# NRF52832_MODULE_V1_0_D.net
KiCad netlist of a schematic drawn in Altium Designer
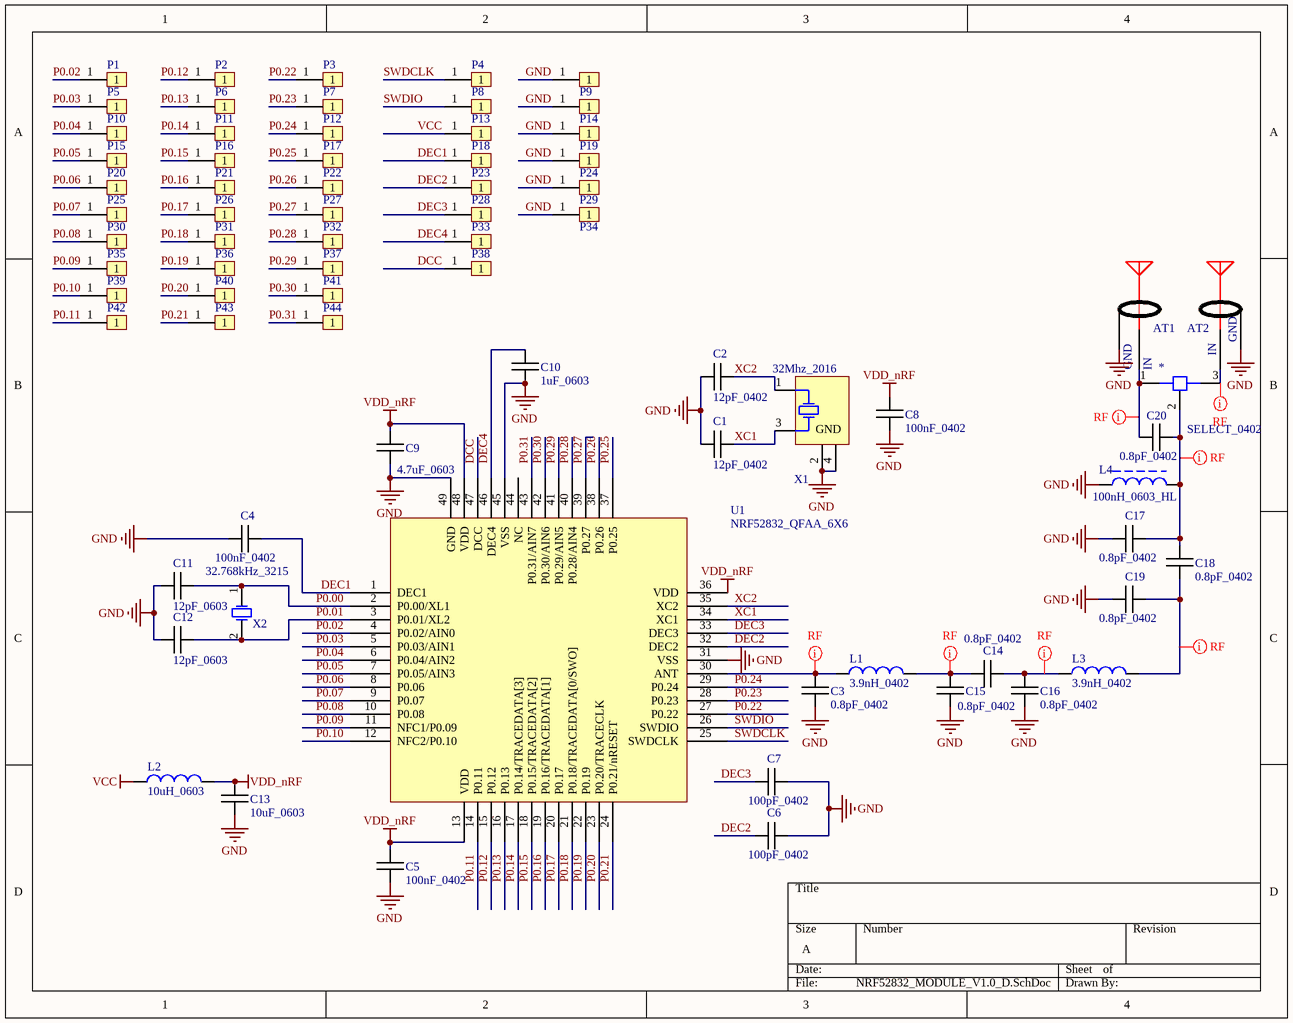
[diagram p0: NRF52832_MODULE_V1.0_D.SchDoc]

(export (version "E")
  (design (tool "Eeschema 10.0.6"))
  (components
    (comp (ref "*")
      (value "SELECT_0402")
      (footprint "PAD 0402_SELECT")
      (libsource (lib "PO_LIBRARY") (part "SELECT_0402"))
    )
    (comp (ref "AT1")
      (value "ANTEN_PCB")
      (footprint "ANTEN_PCB_15MM_L")
      (description "ANTEN_PCB_15MM")
      (libsource (lib "PO_LIBRARY") (part "ANTEN_PCB"))
    )
    (comp (ref "AT2")
      (value "IPX_KK23011-32-7H")
      (footprint "IPEX_ANTENNA")
      (description "ANTEN IPX KK23011-32-7H FOXCONN")
      (libsource (lib "PO_LIBRARY") (part "ANTEN_IPX"))
    )
    (comp (ref "C1")
      (value "12pF_0402")
      (footprint "CAP 0402")
      (libsource (lib "PO_LIBRARY") (part "12pF_0402"))
    )
    (comp (ref "C2")
      (value "12pF_0402")
      (footprint "CAP 0402")
      (libsource (lib "PO_LIBRARY") (part "12pF_0402"))
    )
    (comp (ref "C3")
      (value "0.8pF_0402")
      (footprint "CAP 0402")
      (libsource (lib "PO_LIBRARY") (part "0.8pF_0402"))
    )
    (comp (ref "C4")
      (value "100nF_0402")
      (footprint "CAP 0402")
      (description "104_100nF_0402")
      (libsource (lib "PO_LIBRARY") (part "104_100nF_0402"))
    )
    (comp (ref "C5")
      (value "100nF_0402")
      (footprint "CAP 0402")
      (description "104_100nF_0402")
      (libsource (lib "PO_LIBRARY") (part "104_100nF_0402"))
    )
    (comp (ref "C6")
      (value "100pF_0402")
      (footprint "CAP 0402")
      (description "101_100pF_0402")
      (libsource (lib "PO_LIBRARY") (part "101_100pF_0402"))
    )
    (comp (ref "C7")
      (value "100pF_0402")
      (footprint "CAP 0402")
      (description "101_100pF_0402")
      (libsource (lib "PO_LIBRARY") (part "101_100pF_0402"))
    )
    (comp (ref "C8")
      (value "100nF_0402")
      (footprint "CAP 0402")
      (description "104_100nF_0402")
      (libsource (lib "PO_LIBRARY") (part "104_100nF_0402"))
    )
    (comp (ref "C9")
      (value "4.7uF_0603")
      (footprint "CAP 0603")
      (libsource (lib "PO_LIBRARY") (part "4.7uF_0603"))
    )
    (comp (ref "C10")
      (value "1uF_0603")
      (footprint "CAP 0603")
      (description "1uF_0603 16V")
      (libsource (lib "PO_LIBRARY") (part "105_1uF_0603"))
    )
    (comp (ref "C11")
      (value "12pF_0603")
      (footprint "CAP 0402")
      (description "12pF_0402")
      (libsource (lib "PO_LIBRARY") (part "12pF_0402"))
    )
    (comp (ref "C12")
      (value "12pF_0603")
      (footprint "CAP 0402")
      (description "12pF_0402")
      (libsource (lib "PO_LIBRARY") (part "12pF_0402"))
    )
    (comp (ref "C13")
      (value "10uF_0603")
      (footprint "CAP 0603")
      (description "10uF_0603 16V")
      (libsource (lib "PO_LIBRARY") (part "106_10uF_0603"))
    )
    (comp (ref "C14")
      (value "0.8pF_0402")
      (footprint "CAP 0402")
      (libsource (lib "PO_LIBRARY") (part "0.8pF_0402"))
    )
    (comp (ref "C15")
      (value "0.8pF_0402")
      (footprint "CAP 0402")
      (libsource (lib "PO_LIBRARY") (part "0.8pF_0402"))
    )
    (comp (ref "C16")
      (value "0.8pF_0402")
      (footprint "CAP 0402")
      (libsource (lib "PO_LIBRARY") (part "0.8pF_0402"))
    )
    (comp (ref "C17")
      (value "0.8pF_0402")
      (footprint "CAP 0402")
      (libsource (lib "PO_LIBRARY") (part "0.8pF_0402"))
    )
    (comp (ref "C18")
      (value "0.8pF_0402")
      (footprint "CAP 0402")
      (libsource (lib "PO_LIBRARY") (part "0.8pF_0402"))
    )
    (comp (ref "C19")
      (value "0.8pF_0402")
      (footprint "CAP 0402")
      (libsource (lib "PO_LIBRARY") (part "0.8pF_0402"))
    )
    (comp (ref "C20")
      (value "0.8pF_0402")
      (footprint "CAP 0402")
      (libsource (lib "PO_LIBRARY") (part "0.8pF_0402"))
    )
    (comp (ref "L1")
      (value "3.9nH_0402")
      (footprint "Inductor 0402")
      (libsource (lib "PO_LIBRARY") (part "3.9nH"))
    )
    (comp (ref "L2")
      (value "10uH_0603")
      (footprint "INDUCTOR 0603")
      (libsource (lib "PO_LIBRARY") (part "10uH_0603"))
    )
    (comp (ref "L3")
      (value "3.9nH_0402")
      (footprint "Inductor 0402")
      (libsource (lib "PO_LIBRARY") (part "3.9nH"))
    )
    (comp (ref "L4")
      (value "100nH_0603_HL")
      (footprint "INDUCTOR 0603_HL")
      (description "SDWL1608CR10JSTF Wire Wound Chip Ceramic Inductor")
      (libsource (lib "PO_LIBRARY") (part "100nH_0603_HL"))
    )
    (comp (ref "P1")
      (value "Half-hole 0.6mm")
      (footprint "HALF-HOLE_0.6MM")
      (description "Part Half-hole 0.6mm")
      (libsource (lib "PO_LIBRARY") (part "Half-hole 0.6mm"))
    )
    (comp (ref "P2")
      (value "Half-hole 0.6mm")
      (footprint "HALF-HOLE_0.6MM")
      (description "Part Half-hole 0.6mm")
      (libsource (lib "PO_LIBRARY") (part "Half-hole 0.6mm"))
    )
    (comp (ref "P3")
      (value "Half-hole 0.6mm")
      (footprint "HALF-HOLE_0.6MM")
      (description "Part Half-hole 0.6mm")
      (libsource (lib "PO_LIBRARY") (part "Half-hole 0.6mm"))
    )
    (comp (ref "P4")
      (value "Half-hole 0.6mm")
      (footprint "HALF-HOLE_0.6MM")
      (description "Part Half-hole 0.6mm")
      (libsource (lib "PO_LIBRARY") (part "Half-hole 0.6mm"))
    )
    (comp (ref "P5")
      (value "Half-hole 0.6mm")
      (footprint "HALF-HOLE_0.6MM")
      (description "Part Half-hole 0.6mm")
      (libsource (lib "PO_LIBRARY") (part "Half-hole 0.6mm"))
    )
    (comp (ref "P6")
      (value "Half-hole 0.6mm")
      (footprint "HALF-HOLE_0.6MM")
      (description "Part Half-hole 0.6mm")
      (libsource (lib "PO_LIBRARY") (part "Half-hole 0.6mm"))
    )
    (comp (ref "P7")
      (value "Half-hole 0.6mm")
      (footprint "HALF-HOLE_0.6MM")
      (description "Part Half-hole 0.6mm")
      (libsource (lib "PO_LIBRARY") (part "Half-hole 0.6mm"))
    )
    (comp (ref "P8")
      (value "Half-hole 0.6mm")
      (footprint "HALF-HOLE_0.6MM")
      (description "Part Half-hole 0.6mm")
      (libsource (lib "PO_LIBRARY") (part "Half-hole 0.6mm"))
    )
    (comp (ref "P9")
      (value "Half-hole 0.6mm")
      (footprint "HALF-HOLE_0.6MM")
      (description "Part Half-hole 0.6mm")
      (libsource (lib "PO_LIBRARY") (part "Half-hole 0.6mm"))
    )
    (comp (ref "P10")
      (value "Half-hole 0.6mm")
      (footprint "HALF-HOLE_0.6MM")
      (description "Part Half-hole 0.6mm")
      (libsource (lib "PO_LIBRARY") (part "Half-hole 0.6mm"))
    )
    (comp (ref "P11")
      (value "Half-hole 0.6mm")
      (footprint "HALF-HOLE_0.6MM")
      (description "Part Half-hole 0.6mm")
      (libsource (lib "PO_LIBRARY") (part "Half-hole 0.6mm"))
    )
    (comp (ref "P12")
      (value "Half-hole 0.6mm")
      (footprint "HALF-HOLE_0.6MM")
      (description "Part Half-hole 0.6mm")
      (libsource (lib "PO_LIBRARY") (part "Half-hole 0.6mm"))
    )
    (comp (ref "P13")
      (value "Half-hole 0.6mm")
      (footprint "HALF-HOLE_0.6MM")
      (description "Part Half-hole 0.6mm")
      (libsource (lib "PO_LIBRARY") (part "Half-hole 0.6mm"))
    )
    (comp (ref "P14")
      (value "Half-hole 0.6mm")
      (footprint "HALF-HOLE_0.6MM")
      (description "Part Half-hole 0.6mm")
      (libsource (lib "PO_LIBRARY") (part "Half-hole 0.6mm"))
    )
    (comp (ref "P15")
      (value "Half-hole 0.6mm")
      (footprint "HALF-HOLE_0.6MM")
      (description "Part Half-hole 0.6mm")
      (libsource (lib "PO_LIBRARY") (part "Half-hole 0.6mm"))
    )
    (comp (ref "P16")
      (value "Half-hole 0.6mm")
      (footprint "HALF-HOLE_0.6MM")
      (description "Part Half-hole 0.6mm")
      (libsource (lib "PO_LIBRARY") (part "Half-hole 0.6mm"))
    )
    (comp (ref "P17")
      (value "Half-hole 0.6mm")
      (footprint "HALF-HOLE_0.6MM")
      (description "Part Half-hole 0.6mm")
      (libsource (lib "PO_LIBRARY") (part "Half-hole 0.6mm"))
    )
    (comp (ref "P18")
      (value "Half-hole 0.6mm")
      (footprint "HALF-HOLE_0.6MM")
      (description "Part Half-hole 0.6mm")
      (libsource (lib "PO_LIBRARY") (part "Half-hole 0.6mm"))
    )
    (comp (ref "P19")
      (value "Half-hole 0.6mm")
      (footprint "HALF-HOLE_0.6MM")
      (description "Part Half-hole 0.6mm")
      (libsource (lib "PO_LIBRARY") (part "Half-hole 0.6mm"))
    )
    (comp (ref "P20")
      (value "Half-hole 0.6mm")
      (footprint "HALF-HOLE_0.6MM")
      (description "Part Half-hole 0.6mm")
      (libsource (lib "PO_LIBRARY") (part "Half-hole 0.6mm"))
    )
    (comp (ref "P21")
      (value "Half-hole 0.6mm")
      (footprint "HALF-HOLE_0.6MM")
      (description "Part Half-hole 0.6mm")
      (libsource (lib "PO_LIBRARY") (part "Half-hole 0.6mm"))
    )
    (comp (ref "P22")
      (value "Half-hole 0.6mm")
      (footprint "HALF-HOLE_0.6MM")
      (description "Part Half-hole 0.6mm")
      (libsource (lib "PO_LIBRARY") (part "Half-hole 0.6mm"))
    )
    (comp (ref "P23")
      (value "Half-hole 0.6mm")
      (footprint "HALF-HOLE_0.6MM")
      (description "Part Half-hole 0.6mm")
      (libsource (lib "PO_LIBRARY") (part "Half-hole 0.6mm"))
    )
    (comp (ref "P24")
      (value "Half-hole 0.6mm")
      (footprint "HALF-HOLE_0.6MM")
      (description "Part Half-hole 0.6mm")
      (libsource (lib "PO_LIBRARY") (part "Half-hole 0.6mm"))
    )
    (comp (ref "P25")
      (value "Half-hole 0.6mm")
      (footprint "HALF-HOLE_0.6MM")
      (description "Part Half-hole 0.6mm")
      (libsource (lib "PO_LIBRARY") (part "Half-hole 0.6mm"))
    )
    (comp (ref "P26")
      (value "Half-hole 0.6mm")
      (footprint "HALF-HOLE_0.6MM")
      (description "Part Half-hole 0.6mm")
      (libsource (lib "PO_LIBRARY") (part "Half-hole 0.6mm"))
    )
    (comp (ref "P27")
      (value "Half-hole 0.6mm")
      (footprint "HALF-HOLE_0.6MM")
      (description "Part Half-hole 0.6mm")
      (libsource (lib "PO_LIBRARY") (part "Half-hole 0.6mm"))
    )
    (comp (ref "P28")
      (value "Half-hole 0.6mm")
      (footprint "HALF-HOLE_0.6MM")
      (description "Part Half-hole 0.6mm")
      (libsource (lib "PO_LIBRARY") (part "Half-hole 0.6mm"))
    )
    (comp (ref "P29")
      (value "Half-hole 0.6mm")
      (footprint "HALF-HOLE_0.6MM")
      (description "Part Half-hole 0.6mm")
      (libsource (lib "PO_LIBRARY") (part "Half-hole 0.6mm"))
    )
    (comp (ref "P30")
      (value "Half-hole 0.6mm")
      (footprint "HALF-HOLE_0.6MM")
      (description "Part Half-hole 0.6mm")
      (libsource (lib "PO_LIBRARY") (part "Half-hole 0.6mm"))
    )
    (comp (ref "P31")
      (value "Half-hole 0.6mm")
      (footprint "HALF-HOLE_0.6MM")
      (description "Part Half-hole 0.6mm")
      (libsource (lib "PO_LIBRARY") (part "Half-hole 0.6mm"))
    )
    (comp (ref "P32")
      (value "Half-hole 0.6mm")
      (footprint "HALF-HOLE_0.6MM")
      (description "Part Half-hole 0.6mm")
      (libsource (lib "PO_LIBRARY") (part "Half-hole 0.6mm"))
    )
    (comp (ref "P33")
      (value "Half-hole 0.6mm")
      (footprint "HALF-HOLE_0.6MM")
      (description "Part Half-hole 0.6mm")
      (libsource (lib "PO_LIBRARY") (part "Half-hole 0.6mm"))
    )
    (comp (ref "P34")
      (value "Half-hole 0.6mm")
      (footprint "HALF-HOLE_0.6MM")
      (description "Part Half-hole 0.6mm")
      (libsource (lib "PO_LIBRARY") (part "Half-hole 0.6mm"))
    )
    (comp (ref "P35")
      (value "Half-hole 0.6mm")
      (footprint "HALF-HOLE_0.6MM")
      (description "Part Half-hole 0.6mm")
      (libsource (lib "PO_LIBRARY") (part "Half-hole 0.6mm"))
    )
    (comp (ref "P36")
      (value "Half-hole 0.6mm")
      (footprint "HALF-HOLE_0.6MM")
      (description "Part Half-hole 0.6mm")
      (libsource (lib "PO_LIBRARY") (part "Half-hole 0.6mm"))
    )
    (comp (ref "P37")
      (value "Half-hole 0.6mm")
      (footprint "HALF-HOLE_0.6MM")
      (description "Part Half-hole 0.6mm")
      (libsource (lib "PO_LIBRARY") (part "Half-hole 0.6mm"))
    )
    (comp (ref "P38")
      (value "Half-hole 0.6mm")
      (footprint "HALF-HOLE_0.6MM")
      (description "Part Half-hole 0.6mm")
      (libsource (lib "PO_LIBRARY") (part "Half-hole 0.6mm"))
    )
    (comp (ref "P39")
      (value "Half-hole 0.6mm")
      (footprint "HALF-HOLE_0.6MM")
      (description "Part Half-hole 0.6mm")
      (libsource (lib "PO_LIBRARY") (part "Half-hole 0.6mm"))
    )
    (comp (ref "P40")
      (value "Half-hole 0.6mm")
      (footprint "HALF-HOLE_0.6MM")
      (description "Part Half-hole 0.6mm")
      (libsource (lib "PO_LIBRARY") (part "Half-hole 0.6mm"))
    )
    (comp (ref "P41")
      (value "Half-hole 0.6mm")
      (footprint "HALF-HOLE_0.6MM")
      (description "Part Half-hole 0.6mm")
      (libsource (lib "PO_LIBRARY") (part "Half-hole 0.6mm"))
    )
    (comp (ref "P42")
      (value "Half-hole 0.6mm")
      (footprint "HALF-HOLE_0.6MM")
      (description "Part Half-hole 0.6mm")
      (libsource (lib "PO_LIBRARY") (part "Half-hole 0.6mm"))
    )
    (comp (ref "P43")
      (value "Half-hole 0.6mm")
      (footprint "HALF-HOLE_0.6MM")
      (description "Part Half-hole 0.6mm")
      (libsource (lib "PO_LIBRARY") (part "Half-hole 0.6mm"))
    )
    (comp (ref "P44")
      (value "Half-hole 0.6mm")
      (footprint "HALF-HOLE_0.6MM")
      (description "Part Half-hole 0.6mm")
      (libsource (lib "PO_LIBRARY") (part "Half-hole 0.6mm"))
    )
    (comp (ref "U1")
      (value "NRF52832_QFAA_6X6")
      (footprint "QFN48_6X6")
      (libsource (lib "PO_LIBRARY") (part "NRF52832"))
    )
    (comp (ref "X1")
      (value "32Mhz_2016")
      (footprint "CYSTAL-SMD-2016")
      (libsource (lib "PO_LIBRARY") (part "Crystal 2016 32MHz"))
    )
    (comp (ref "X2")
      (value "32.768kHz_3215")
      (footprint "CYSTAL-SMD-3215")
      (description "Crystal 3215 32.768kHz")
      (libsource (lib "PO_LIBRARY") (part "Crystal 3215 32.768kHz"))
    )
  )
  (nets
    (net (code "1") (name "/DCC") (class "Default")
      (node (ref "P38") (pin "1") (pinfunction "1_1") (pintype "passive"))
      (node (ref "U1") (pin "47") (pinfunction "DCC_47") (pintype "passive"))
    )
    (net (code "2") (name "/DEC1") (class "Default")
      (node (ref "C4") (pin "2") (pinfunction "2_2") (pintype "passive"))
      (node (ref "P18") (pin "1") (pinfunction "1_1") (pintype "passive"))
      (node (ref "U1") (pin "1") (pinfunction "DEC1_1") (pintype "passive"))
    )
    (net (code "3") (name "/DEC2") (class "Default")
      (node (ref "C6") (pin "1") (pinfunction "1_1") (pintype "passive"))
      (node (ref "P23") (pin "1") (pinfunction "1_1") (pintype "passive"))
      (node (ref "U1") (pin "32") (pinfunction "DEC2_32") (pintype "passive"))
    )
    (net (code "4") (name "/DEC3") (class "Default")
      (node (ref "C7") (pin "1") (pinfunction "1_1") (pintype "passive"))
      (node (ref "P28") (pin "1") (pinfunction "1_1") (pintype "passive"))
      (node (ref "U1") (pin "33") (pinfunction "DEC3_33") (pintype "passive"))
    )
    (net (code "5") (name "/DEC4") (class "Default")
      (node (ref "C10") (pin "2") (pinfunction "2_2") (pintype "passive"))
      (node (ref "P33") (pin "1") (pinfunction "1_1") (pintype "passive"))
      (node (ref "U1") (pin "46") (pinfunction "DEC4_46") (pintype "passive"))
    )
    (net (code "6") (name "/P0.00") (class "Default")
      (node (ref "C11") (pin "1") (pinfunction "1_1") (pintype "passive"))
      (node (ref "U1") (pin "2") (pinfunction "P0.00/XL1_2") (pintype "passive"))
      (node (ref "X2") (pin "1") (pinfunction "XTAL_1") (pintype "passive"))
    )
    (net (code "7") (name "/P0.01") (class "Default")
      (node (ref "C12") (pin "1") (pinfunction "1_1") (pintype "passive"))
      (node (ref "U1") (pin "3") (pinfunction "P0.01/XL2_3") (pintype "passive"))
      (node (ref "X2") (pin "2") (pinfunction "XTAL_2") (pintype "passive"))
    )
    (net (code "8") (name "/P0.02") (class "Default")
      (node (ref "P1") (pin "1") (pinfunction "1_1") (pintype "passive"))
      (node (ref "U1") (pin "4") (pinfunction "P0.02/AIN0_4") (pintype "passive"))
    )
    (net (code "9") (name "/P0.03") (class "Default")
      (node (ref "P5") (pin "1") (pinfunction "1_1") (pintype "passive"))
      (node (ref "U1") (pin "5") (pinfunction "P0.03/AIN1_5") (pintype "passive"))
    )
    (net (code "10") (name "/P0.04") (class "Default")
      (node (ref "P10") (pin "1") (pinfunction "1_1") (pintype "passive"))
      (node (ref "U1") (pin "6") (pinfunction "P0.04/AIN2_6") (pintype "passive"))
    )
    (net (code "11") (name "/P0.05") (class "Default")
      (node (ref "P15") (pin "1") (pinfunction "1_1") (pintype "passive"))
      (node (ref "U1") (pin "7") (pinfunction "P0.05/AIN3_7") (pintype "passive"))
    )
    (net (code "12") (name "/P0.06") (class "Default")
      (node (ref "P20") (pin "1") (pinfunction "1_1") (pintype "passive"))
      (node (ref "U1") (pin "8") (pinfunction "P0.06_8") (pintype "passive"))
    )
    (net (code "13") (name "/P0.07") (class "Default")
      (node (ref "P25") (pin "1") (pinfunction "1_1") (pintype "passive"))
      (node (ref "U1") (pin "9") (pinfunction "P0.07_9") (pintype "passive"))
    )
    (net (code "14") (name "/P0.08") (class "Default")
      (node (ref "P30") (pin "1") (pinfunction "1_1") (pintype "passive"))
      (node (ref "U1") (pin "10") (pinfunction "P0.08_10") (pintype "passive"))
    )
    (net (code "15") (name "/P0.09") (class "Default")
      (node (ref "P35") (pin "1") (pinfunction "1_1") (pintype "passive"))
      (node (ref "U1") (pin "11") (pinfunction "NFC1/P0.09_11") (pintype "passive"))
    )
    (net (code "16") (name "/P0.10") (class "Default")
      (node (ref "P39") (pin "1") (pinfunction "1_1") (pintype "passive"))
      (node (ref "U1") (pin "12") (pinfunction "NFC2/P0.10_12") (pintype "passive"))
    )
    (net (code "17") (name "/P0.11") (class "Default")
      (node (ref "P42") (pin "1") (pinfunction "1_1") (pintype "passive"))
      (node (ref "U1") (pin "14") (pinfunction "P0.11_14") (pintype "passive"))
    )
    (net (code "18") (name "/P0.12") (class "Default")
      (node (ref "P2") (pin "1") (pinfunction "1_1") (pintype "passive"))
      (node (ref "U1") (pin "15") (pinfunction "P0.12_15") (pintype "passive"))
    )
    (net (code "19") (name "/P0.13") (class "Default")
      (node (ref "P6") (pin "1") (pinfunction "1_1") (pintype "passive"))
      (node (ref "U1") (pin "16") (pinfunction "P0.13_16") (pintype "passive"))
    )
    (net (code "20") (name "/P0.14") (class "Default")
      (node (ref "P11") (pin "1") (pinfunction "1_1") (pintype "passive"))
      (node (ref "U1") (pin "17") (pinfunction "P0.14/TRACEDATA[3]_17") (pintype "passive"))
    )
    (net (code "21") (name "/P0.15") (class "Default")
      (node (ref "P16") (pin "1") (pinfunction "1_1") (pintype "passive"))
      (node (ref "U1") (pin "18") (pinfunction "P0.15/TRACEDATA[2]_18") (pintype "passive"))
    )
    (net (code "22") (name "/P0.16") (class "Default")
      (node (ref "P21") (pin "1") (pinfunction "1_1") (pintype "passive"))
      (node (ref "U1") (pin "19") (pinfunction "P0.16/TRACEDATA[1]_19") (pintype "passive"))
    )
    (net (code "23") (name "/P0.17") (class "Default")
      (node (ref "P26") (pin "1") (pinfunction "1_1") (pintype "passive"))
      (node (ref "U1") (pin "20") (pinfunction "P0.17_20") (pintype "passive"))
    )
    (net (code "24") (name "/P0.18") (class "Default")
      (node (ref "P31") (pin "1") (pinfunction "1_1") (pintype "passive"))
      (node (ref "U1") (pin "21") (pinfunction "P0.18/TRACEDATA[0/SWO]_21") (pintype "passive"))
    )
    (net (code "25") (name "/P0.19") (class "Default")
      (node (ref "P36") (pin "1") (pinfunction "1_1") (pintype "passive"))
      (node (ref "U1") (pin "22") (pinfunction "P0.19_22") (pintype "passive"))
    )
    (net (code "26") (name "/P0.20") (class "Default")
      (node (ref "P40") (pin "1") (pinfunction "1_1") (pintype "passive"))
      (node (ref "U1") (pin "23") (pinfunction "P0.20/TRACECLK_23") (pintype "passive"))
    )
    (net (code "27") (name "/P0.21") (class "Default")
      (node (ref "P43") (pin "1") (pinfunction "1_1") (pintype "passive"))
      (node (ref "U1") (pin "24") (pinfunction "P0.21/nRESET_24") (pintype "passive"))
    )
    (net (code "28") (name "/P0.22") (class "Default")
      (node (ref "P3") (pin "1") (pinfunction "1_1") (pintype "passive"))
      (node (ref "U1") (pin "27") (pinfunction "P0.22_27") (pintype "passive"))
    )
    (net (code "29") (name "/P0.23") (class "Default")
      (node (ref "P7") (pin "1") (pinfunction "1_1") (pintype "passive"))
      (node (ref "U1") (pin "28") (pinfunction "P0.23_28") (pintype "passive"))
    )
    (net (code "30") (name "/P0.24") (class "Default")
      (node (ref "P12") (pin "1") (pinfunction "1_1") (pintype "passive"))
      (node (ref "U1") (pin "29") (pinfunction "P0.24_29") (pintype "passive"))
    )
    (net (code "31") (name "/P0.25") (class "Default")
      (node (ref "P17") (pin "1") (pinfunction "1_1") (pintype "passive"))
      (node (ref "U1") (pin "37") (pinfunction "P0.25_37") (pintype "passive"))
    )
    (net (code "32") (name "/P0.26") (class "Default")
      (node (ref "P22") (pin "1") (pinfunction "1_1") (pintype "passive"))
      (node (ref "U1") (pin "38") (pinfunction "P0.26_38") (pintype "passive"))
    )
    (net (code "33") (name "/P0.27") (class "Default")
      (node (ref "P27") (pin "1") (pinfunction "1_1") (pintype "passive"))
      (node (ref "U1") (pin "39") (pinfunction "P0.27_39") (pintype "passive"))
    )
    (net (code "34") (name "/P0.28") (class "Default")
      (node (ref "P32") (pin "1") (pinfunction "1_1") (pintype "passive"))
      (node (ref "U1") (pin "40") (pinfunction "P0.28/AIN4_40") (pintype "passive"))
    )
    (net (code "35") (name "/P0.29") (class "Default")
      (node (ref "P37") (pin "1") (pinfunction "1_1") (pintype "passive"))
      (node (ref "U1") (pin "41") (pinfunction "P0.29/AIN5_41") (pintype "passive"))
    )
    (net (code "36") (name "/P0.30") (class "Default")
      (node (ref "P41") (pin "1") (pinfunction "1_1") (pintype "passive"))
      (node (ref "U1") (pin "42") (pinfunction "P0.30/AIN6_42") (pintype "passive"))
    )
    (net (code "37") (name "/P0.31") (class "Default")
      (node (ref "P44") (pin "1") (pinfunction "1_1") (pintype "passive"))
      (node (ref "U1") (pin "43") (pinfunction "P0.31/AIN7_43") (pintype "passive"))
    )
    (net (code "38") (name "/SWDCLK") (class "Default")
      (node (ref "P4") (pin "1") (pinfunction "1_1") (pintype "passive"))
      (node (ref "U1") (pin "25") (pinfunction "SWDCLK_25") (pintype "passive"))
    )
    (net (code "39") (name "/SWDIO") (class "Default")
      (node (ref "P8") (pin "1") (pinfunction "1_1") (pintype "passive"))
      (node (ref "U1") (pin "26") (pinfunction "SWDIO_26") (pintype "passive"))
    )
    (net (code "40") (name "/XC1") (class "Default")
      (node (ref "C1") (pin "2") (pinfunction "2_2") (pintype "passive"))
      (node (ref "U1") (pin "34") (pinfunction "XC1_34") (pintype "passive"))
      (node (ref "X1") (pin "3") (pinfunction "XTAL_3") (pintype "passive"))
    )
    (net (code "41") (name "/XC2") (class "Default")
      (node (ref "C2") (pin "2") (pinfunction "2_2") (pintype "passive"))
      (node (ref "U1") (pin "35") (pinfunction "XC2_35") (pintype "passive"))
      (node (ref "X1") (pin "1") (pinfunction "XTAL_1") (pintype "passive"))
    )
    (net (code "42") (name "GND") (class "Default")
      (node (ref "AT1") (pin "2") (pinfunction "GND_2") (pintype "passive"))
      (node (ref "AT2") (pin "2") (pinfunction "GND_2") (pintype "passive"))
      (node (ref "C1") (pin "1") (pinfunction "1_1") (pintype "passive"))
      (node (ref "C10") (pin "1") (pinfunction "1_1") (pintype "passive"))
      (node (ref "C11") (pin "2") (pinfunction "2_2") (pintype "passive"))
      (node (ref "C12") (pin "2") (pinfunction "2_2") (pintype "passive"))
      (node (ref "C13") (pin "1") (pinfunction "1_1") (pintype "passive"))
      (node (ref "C15") (pin "1") (pinfunction "1_1") (pintype "passive"))
      (node (ref "C16") (pin "1") (pinfunction "1_1") (pintype "passive"))
      (node (ref "C17") (pin "1") (pinfunction "1_1") (pintype "passive"))
      (node (ref "C19") (pin "1") (pinfunction "1_1") (pintype "passive"))
      (node (ref "C2") (pin "1") (pinfunction "1_1") (pintype "passive"))
      (node (ref "C3") (pin "1") (pinfunction "1_1") (pintype "passive"))
      (node (ref "C4") (pin "1") (pinfunction "1_1") (pintype "passive"))
      (node (ref "C5") (pin "1") (pinfunction "1_1") (pintype "passive"))
      (node (ref "C6") (pin "2") (pinfunction "2_2") (pintype "passive"))
      (node (ref "C7") (pin "2") (pinfunction "2_2") (pintype "passive"))
      (node (ref "C8") (pin "1") (pinfunction "1_1") (pintype "passive"))
      (node (ref "C9") (pin "1") (pinfunction "1_1") (pintype "passive"))
      (node (ref "L4") (pin "1") (pinfunction "1_1") (pintype "passive"))
      (node (ref "P14") (pin "1") (pinfunction "1_1") (pintype "passive"))
      (node (ref "P19") (pin "1") (pinfunction "1_1") (pintype "passive"))
      (node (ref "P24") (pin "1") (pinfunction "1_1") (pintype "passive"))
      (node (ref "P29") (pin "1") (pinfunction "1_1") (pintype "passive"))
      (node (ref "P34") (pin "1") (pinfunction "1_1") (pintype "passive"))
      (node (ref "P9") (pin "1") (pinfunction "1_1") (pintype "passive"))
      (node (ref "U1") (pin "31") (pinfunction "VSS_31") (pintype "passive"))
      (node (ref "U1") (pin "45") (pinfunction "VSS_45") (pintype "passive"))
      (node (ref "U1") (pin "49") (pinfunction "GND_49") (pintype "passive"))
      (node (ref "X1") (pin "2") (pinfunction "GND_2") (pintype "power_in"))
      (node (ref "X1") (pin "4") (pinfunction "GND_4") (pintype "power_in"))
    )
    (net (code "43") (name "Net-(*-Pad2)") (class "Default")
      (node (ref "*") (pin "2") (pinfunction "2_2") (pintype "passive"))
      (node (ref "C17") (pin "2") (pinfunction "2_2") (pintype "passive"))
      (node (ref "C18") (pin "2") (pinfunction "2_2") (pintype "passive"))
      (node (ref "C20") (pin "2") (pinfunction "2_2") (pintype "passive"))
      (node (ref "L4") (pin "2") (pinfunction "2_2") (pintype "passive"))
    )
    (net (code "44") (name "Net-(AT1-IN)") (class "Default")
      (node (ref "*") (pin "1") (pinfunction "1_1") (pintype "passive"))
      (node (ref "AT1") (pin "1") (pinfunction "IN_1") (pintype "passive"))
      (node (ref "C20") (pin "1") (pinfunction "1_1") (pintype "passive"))
    )
    (net (code "45") (name "Net-(AT2-IN)") (class "Default")
      (node (ref "*") (pin "3") (pinfunction "3_3") (pintype "passive"))
      (node (ref "AT2") (pin "1") (pinfunction "IN_1") (pintype "passive"))
    )
    (net (code "46") (name "Net-(C14-Pad1)") (class "Default")
      (node (ref "C14") (pin "1") (pinfunction "1_1") (pintype "passive"))
      (node (ref "C16") (pin "2") (pinfunction "2_2") (pintype "passive"))
      (node (ref "L3") (pin "1") (pinfunction "1_1") (pintype "passive"))
    )
    (net (code "47") (name "Net-(C14-Pad2)") (class "Default")
      (node (ref "C14") (pin "2") (pinfunction "2_2") (pintype "passive"))
      (node (ref "C15") (pin "2") (pinfunction "2_2") (pintype "passive"))
      (node (ref "L1") (pin "2") (pinfunction "2_2") (pintype "passive"))
    )
    (net (code "48") (name "Net-(C18-Pad1)") (class "Default")
      (node (ref "C18") (pin "1") (pinfunction "1_1") (pintype "passive"))
      (node (ref "C19") (pin "2") (pinfunction "2_2") (pintype "passive"))
      (node (ref "L3") (pin "2") (pinfunction "2_2") (pintype "passive"))
    )
    (net (code "49") (name "Net-(U1-ANT)") (class "Default")
      (node (ref "C3") (pin "2") (pinfunction "2_2") (pintype "passive"))
      (node (ref "L1") (pin "1") (pinfunction "1_1") (pintype "passive"))
      (node (ref "U1") (pin "30") (pinfunction "ANT_30") (pintype "passive"))
    )
    (net (code "50") (name "VCC") (class "Default")
      (node (ref "L2") (pin "1") (pinfunction "1_1") (pintype "passive"))
      (node (ref "P13") (pin "1") (pinfunction "1_1") (pintype "passive"))
    )
    (net (code "51") (name "VDD_nRF") (class "Default")
      (node (ref "C13") (pin "2") (pinfunction "2_2") (pintype "passive"))
      (node (ref "C5") (pin "2") (pinfunction "2_2") (pintype "passive"))
      (node (ref "C8") (pin "2") (pinfunction "2_2") (pintype "passive"))
      (node (ref "C9") (pin "2") (pinfunction "2_2") (pintype "passive"))
      (node (ref "L2") (pin "2") (pinfunction "2_2") (pintype "passive"))
      (node (ref "U1") (pin "13") (pinfunction "VDD_13") (pintype "passive"))
      (node (ref "U1") (pin "36") (pinfunction "VDD_36") (pintype "passive"))
      (node (ref "U1") (pin "48") (pinfunction "VDD_48") (pintype "passive"))
    )
    (net (code "52") (name "unconnected-(U1-NC-Pad44)") (class "Default")
      (node (ref "U1") (pin "44") (pinfunction "NC_44") (pintype "passive"))
    )
  )
)
